# SH6_-_CAN.net
KiCad netlist of a schematic drawn in Altium Designer
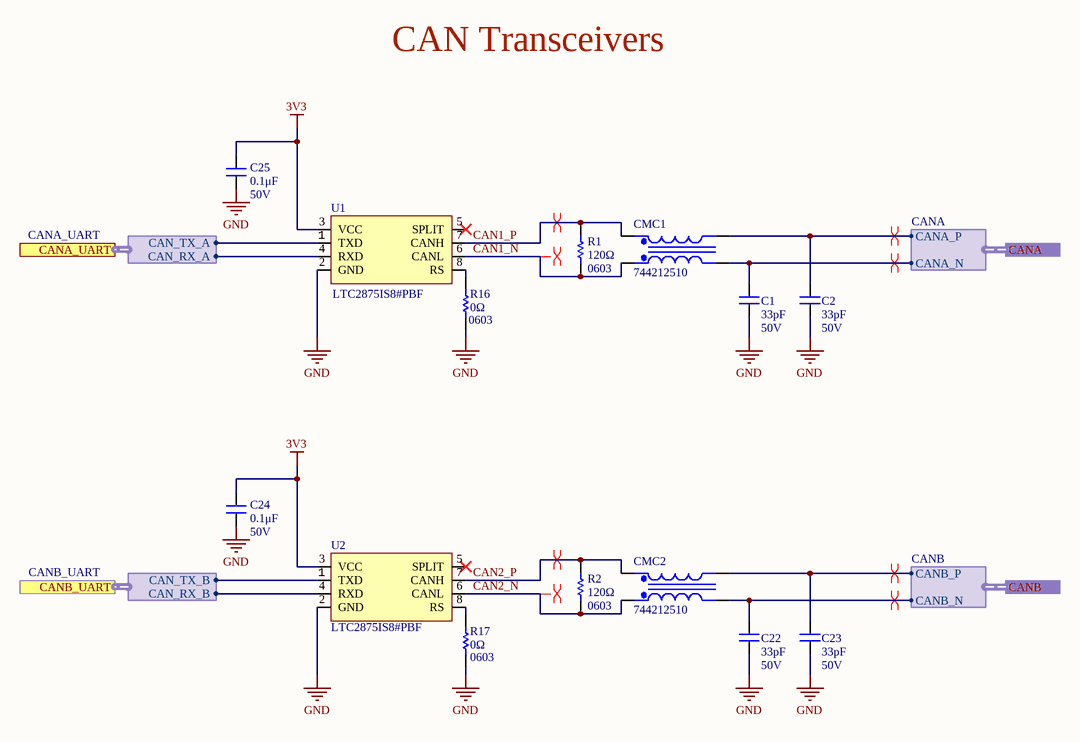
[diagram p0: SH6 - CAN.SchDoc]

(export (version "E")
  (design (tool "Eeschema 10.0.6"))
  (components
    (comp (ref "C1")
      (value "33pF")
      (footprint "CAP0603")
      (description "CAP CER 33PF 50V C0G/NP0")
      (fields
        (field (name "TOLERANCE") "5%")
        (field (name "VOLTAGE") "50V")
        (field (name "Comment") "CAP_33pF_50V_0603")
      )
      (libsource (lib "UWRT_Schematic_Library_2020") (part "CAP_33pF_50V_0603"))
    )
    (comp (ref "C2")
      (value "33pF")
      (footprint "CAP0603")
      (description "CAP CER 33PF 50V C0G/NP0")
      (fields
        (field (name "TOLERANCE") "5%")
        (field (name "VOLTAGE") "50V")
        (field (name "Comment") "CAP_33pF_50V_0603")
      )
      (libsource (lib "UWRT_Schematic_Library_2020") (part "CAP_33pF_50V_0603"))
    )
    (comp (ref "C22")
      (value "33pF")
      (footprint "CAP0603")
      (description "CAP CER 33PF 50V C0G/NP0")
      (fields
        (field (name "TOLERANCE") "5%")
        (field (name "VOLTAGE") "50V")
        (field (name "Comment") "CAP_33pF_50V_0603")
      )
      (libsource (lib "UWRT_Schematic_Library_2020") (part "CAP_33pF_50V_0603"))
    )
    (comp (ref "C23")
      (value "33pF")
      (footprint "CAP0603")
      (description "CAP CER 33PF 50V C0G/NP0")
      (fields
        (field (name "TOLERANCE") "5%")
        (field (name "VOLTAGE") "50V")
        (field (name "Comment") "CAP_33pF_50V_0603")
      )
      (libsource (lib "UWRT_Schematic_Library_2020") (part "CAP_33pF_50V_0603"))
    )
    (comp (ref "C24")
      (value "0.1μF")
      (footprint "CAP0603")
      (description "CAP CER 0.1UF 50V X7R 0603")
      (fields (field (name "VOLTAGE RATING") "50V") (field (name "Comment") "CAP_0.1uF_50V_0603"))
      (libsource (lib "UWRT_Schematic_Library_2020") (part "CAP_0.1uF_50V_0603"))
    )
    (comp (ref "C25")
      (value "0.1μF")
      (footprint "CAP0603")
      (description "CAP CER 0.1UF 50V X7R 0603")
      (fields (field (name "VOLTAGE RATING") "50V") (field (name "Comment") "CAP_0.1uF_50V_0603"))
      (libsource (lib "UWRT_Schematic_Library_2020") (part "CAP_0.1uF_50V_0603"))
    )
    (comp (ref "CMC1")
      (value "CMC_51uH")
      (footprint "744212510")
      (description "CMC 51uH 300MA 2LN SMD")
      (fields (field (name "MANUFACTURER PART NUMBER 1") "744212510") (field (name "TOLERANCE") "50%"))
      (libsource (lib "UWRT_Schematic_Library_2020") (part "CMC_51uH"))
    )
    (comp (ref "CMC2")
      (value "CMC_51uH")
      (footprint "744212510")
      (description "CMC 51uH 300MA 2LN SMD")
      (fields (field (name "MANUFACTURER PART NUMBER 1") "744212510") (field (name "TOLERANCE") "50%"))
      (libsource (lib "UWRT_Schematic_Library_2020") (part "CMC_51uH"))
    )
    (comp (ref "R1")
      (value "120Ω")
      (footprint "RESC0603(1608)_N")
      (description "RES 120 OHM 5% 1/10W 0603")
      (fields
        (field (name "TOLERANCE") "5%")
        (field (name "CASE CODE (IMPERIAL)") "0603")
        (field (name "Comment") "RES_120Ω_0603")
      )
      (libsource (lib "UWRT_Schematic_Library_2020") (part "RES_120Ω_0603_5%"))
    )
    (comp (ref "R2")
      (value "120Ω")
      (footprint "RESC0603(1608)_N")
      (description "RES 120 OHM 5% 1/10W 0603")
      (fields
        (field (name "TOLERANCE") "5%")
        (field (name "CASE CODE (IMPERIAL)") "0603")
        (field (name "Comment") "RES_120Ω_0603")
      )
      (libsource (lib "UWRT_Schematic_Library_2020") (part "RES_120Ω_0603_5%"))
    )
    (comp (ref "R16")
      (value "0Ω")
      (footprint "RESC0603(1608)_N")
      (description "RES 0 OHM JUMPER 1/10W 0603")
      (fields (field (name "CASE CODE (IMPERIAL)") "0603") (field (name "Comment") "RES_0Ω_0603"))
      (libsource (lib "UWRT_Schematic_Library_2020") (part "RES_0Ω_0603"))
    )
    (comp (ref "R17")
      (value "0Ω")
      (footprint "RESC0603(1608)_N")
      (description "RES 0 OHM JUMPER 1/10W 0603")
      (fields (field (name "CASE CODE (IMPERIAL)") "0603") (field (name "Comment") "RES_0Ω_0603"))
      (libsource (lib "UWRT_Schematic_Library_2020") (part "RES_0Ω_0603"))
    )
    (comp (ref "U1")
      (value "IC TXRX CAN")
      (footprint "LT-S8_N")
      (description "IC TXRX CAN 4MBPS 8SO")
      (fields (field (name "MANUFACTURER PART NUMBER 1") "LTC2875IS8#PBF"))
      (libsource (lib "UWRT_Schematic_Library_2020") (part "LTC2875"))
    )
    (comp (ref "U2")
      (value "IC TXRX CAN")
      (footprint "LT-S8_N")
      (description "IC TXRX CAN 4MBPS 8SO")
      (fields (field (name "MANUFACTURER PART NUMBER 1") "LTC2875IS8#PBF"))
      (libsource (lib "UWRT_Schematic_Library_2020") (part "LTC2875"))
    )
  )
  (nets
    (net (code "5") (name "/CAN1_N") (class "Default")
      (node (ref "CMC1") (pin "1") (pinfunction "Pri+_1") (pintype "passive"))
      (node (ref "R1") (pin "1") (pinfunction "1_1") (pintype "passive"))
      (node (ref "U1") (pin "6") (pinfunction "CANL_6") (pintype "passive"))
    )
    (net (code "6") (name "/CAN1_P") (class "Default")
      (node (ref "CMC1") (pin "3") (pinfunction "Sec+_3") (pintype "passive"))
      (node (ref "R1") (pin "2") (pinfunction "2_2") (pintype "passive"))
      (node (ref "U1") (pin "7") (pinfunction "CANH_7") (pintype "passive"))
    )
    (net (code "7") (name "/CAN2_N") (class "Default")
      (node (ref "CMC2") (pin "1") (pinfunction "Pri+_1") (pintype "passive"))
      (node (ref "R2") (pin "1") (pinfunction "1_1") (pintype "passive"))
      (node (ref "U2") (pin "6") (pinfunction "CANL_6") (pintype "passive"))
    )
    (net (code "8") (name "/CAN2_P") (class "Default")
      (node (ref "CMC2") (pin "3") (pinfunction "Sec+_3") (pintype "passive"))
      (node (ref "R2") (pin "2") (pinfunction "2_2") (pintype "passive"))
      (node (ref "U2") (pin "7") (pinfunction "CANH_7") (pintype "passive"))
    )
    (net (code "9") (name "/CANA_N") (class "Default")
      (node (ref "C1") (pin "2") (pinfunction "2_2") (pintype "passive"))
      (node (ref "CMC1") (pin "5") (pinfunction "Pri-_5") (pintype "passive"))
    )
    (net (code "10") (name "/CANA_P") (class "Default")
      (node (ref "C2") (pin "2") (pinfunction "2_2") (pintype "passive"))
      (node (ref "CMC1") (pin "4") (pinfunction "Sec-_4") (pintype "passive"))
    )
    (net (code "11") (name "/CANB_N") (class "Default")
      (node (ref "C22") (pin "2") (pinfunction "2_2") (pintype "passive"))
      (node (ref "CMC2") (pin "5") (pinfunction "Pri-_5") (pintype "passive"))
    )
    (net (code "12") (name "/CANB_P") (class "Default")
      (node (ref "C23") (pin "2") (pinfunction "2_2") (pintype "passive"))
      (node (ref "CMC2") (pin "4") (pinfunction "Sec-_4") (pintype "passive"))
    )
    (net (code "13") (name "/CAN_RX_A") (class "Default")
      (node (ref "U1") (pin "4") (pinfunction "RXD_4") (pintype "passive"))
    )
    (net (code "14") (name "/CAN_RX_B") (class "Default")
      (node (ref "U2") (pin "4") (pinfunction "RXD_4") (pintype "passive"))
    )
    (net (code "15") (name "/CAN_TX_A") (class "Default")
      (node (ref "U1") (pin "1") (pinfunction "TXD_1") (pintype "passive"))
    )
    (net (code "16") (name "/CAN_TX_B") (class "Default")
      (node (ref "U2") (pin "1") (pinfunction "TXD_1") (pintype "passive"))
    )
    (net (code "21") (name "3V3") (class "Default")
      (node (ref "C24") (pin "1") (pinfunction "1_1") (pintype "passive"))
      (node (ref "C25") (pin "1") (pinfunction "1_1") (pintype "passive"))
      (node (ref "U1") (pin "3") (pinfunction "VCC_3") (pintype "passive"))
      (node (ref "U2") (pin "3") (pinfunction "VCC_3") (pintype "passive"))
    )
    (net (code "22") (name "GND") (class "Default")
      (node (ref "C1") (pin "1") (pinfunction "1_1") (pintype "passive"))
      (node (ref "C2") (pin "1") (pinfunction "1_1") (pintype "passive"))
      (node (ref "C22") (pin "1") (pinfunction "1_1") (pintype "passive"))
      (node (ref "C23") (pin "1") (pinfunction "1_1") (pintype "passive"))
      (node (ref "C24") (pin "2") (pinfunction "2_2") (pintype "passive"))
      (node (ref "C25") (pin "2") (pinfunction "2_2") (pintype "passive"))
      (node (ref "R16") (pin "1") (pinfunction "1_1") (pintype "passive"))
      (node (ref "R17") (pin "1") (pinfunction "1_1") (pintype "passive"))
      (node (ref "U1") (pin "2") (pinfunction "GND_2") (pintype "passive"))
      (node (ref "U2") (pin "2") (pinfunction "GND_2") (pintype "passive"))
    )
    (net (code "23") (name "Net-(U1-RS)") (class "Default")
      (node (ref "R16") (pin "2") (pinfunction "2_2") (pintype "passive"))
      (node (ref "U1") (pin "8") (pinfunction "RS_8") (pintype "passive"))
    )
    (net (code "24") (name "Net-(U2-RS)") (class "Default")
      (node (ref "R17") (pin "2") (pinfunction "2_2") (pintype "passive"))
      (node (ref "U2") (pin "8") (pinfunction "RS_8") (pintype "passive"))
    )
    (net (code "25") (name "unconnected-(U1-SPLIT-Pad5)") (class "Default")
      (node (ref "U1") (pin "5") (pinfunction "SPLIT_5") (pintype "passive+no_connect"))
    )
    (net (code "26") (name "unconnected-(U2-SPLIT-Pad5)") (class "Default")
      (node (ref "U2") (pin "5") (pinfunction "SPLIT_5") (pintype "passive+no_connect"))
    )
  )
)
